# Bowlong_Machine.net
KiCad netlist of a schematic drawn in Altium Designer
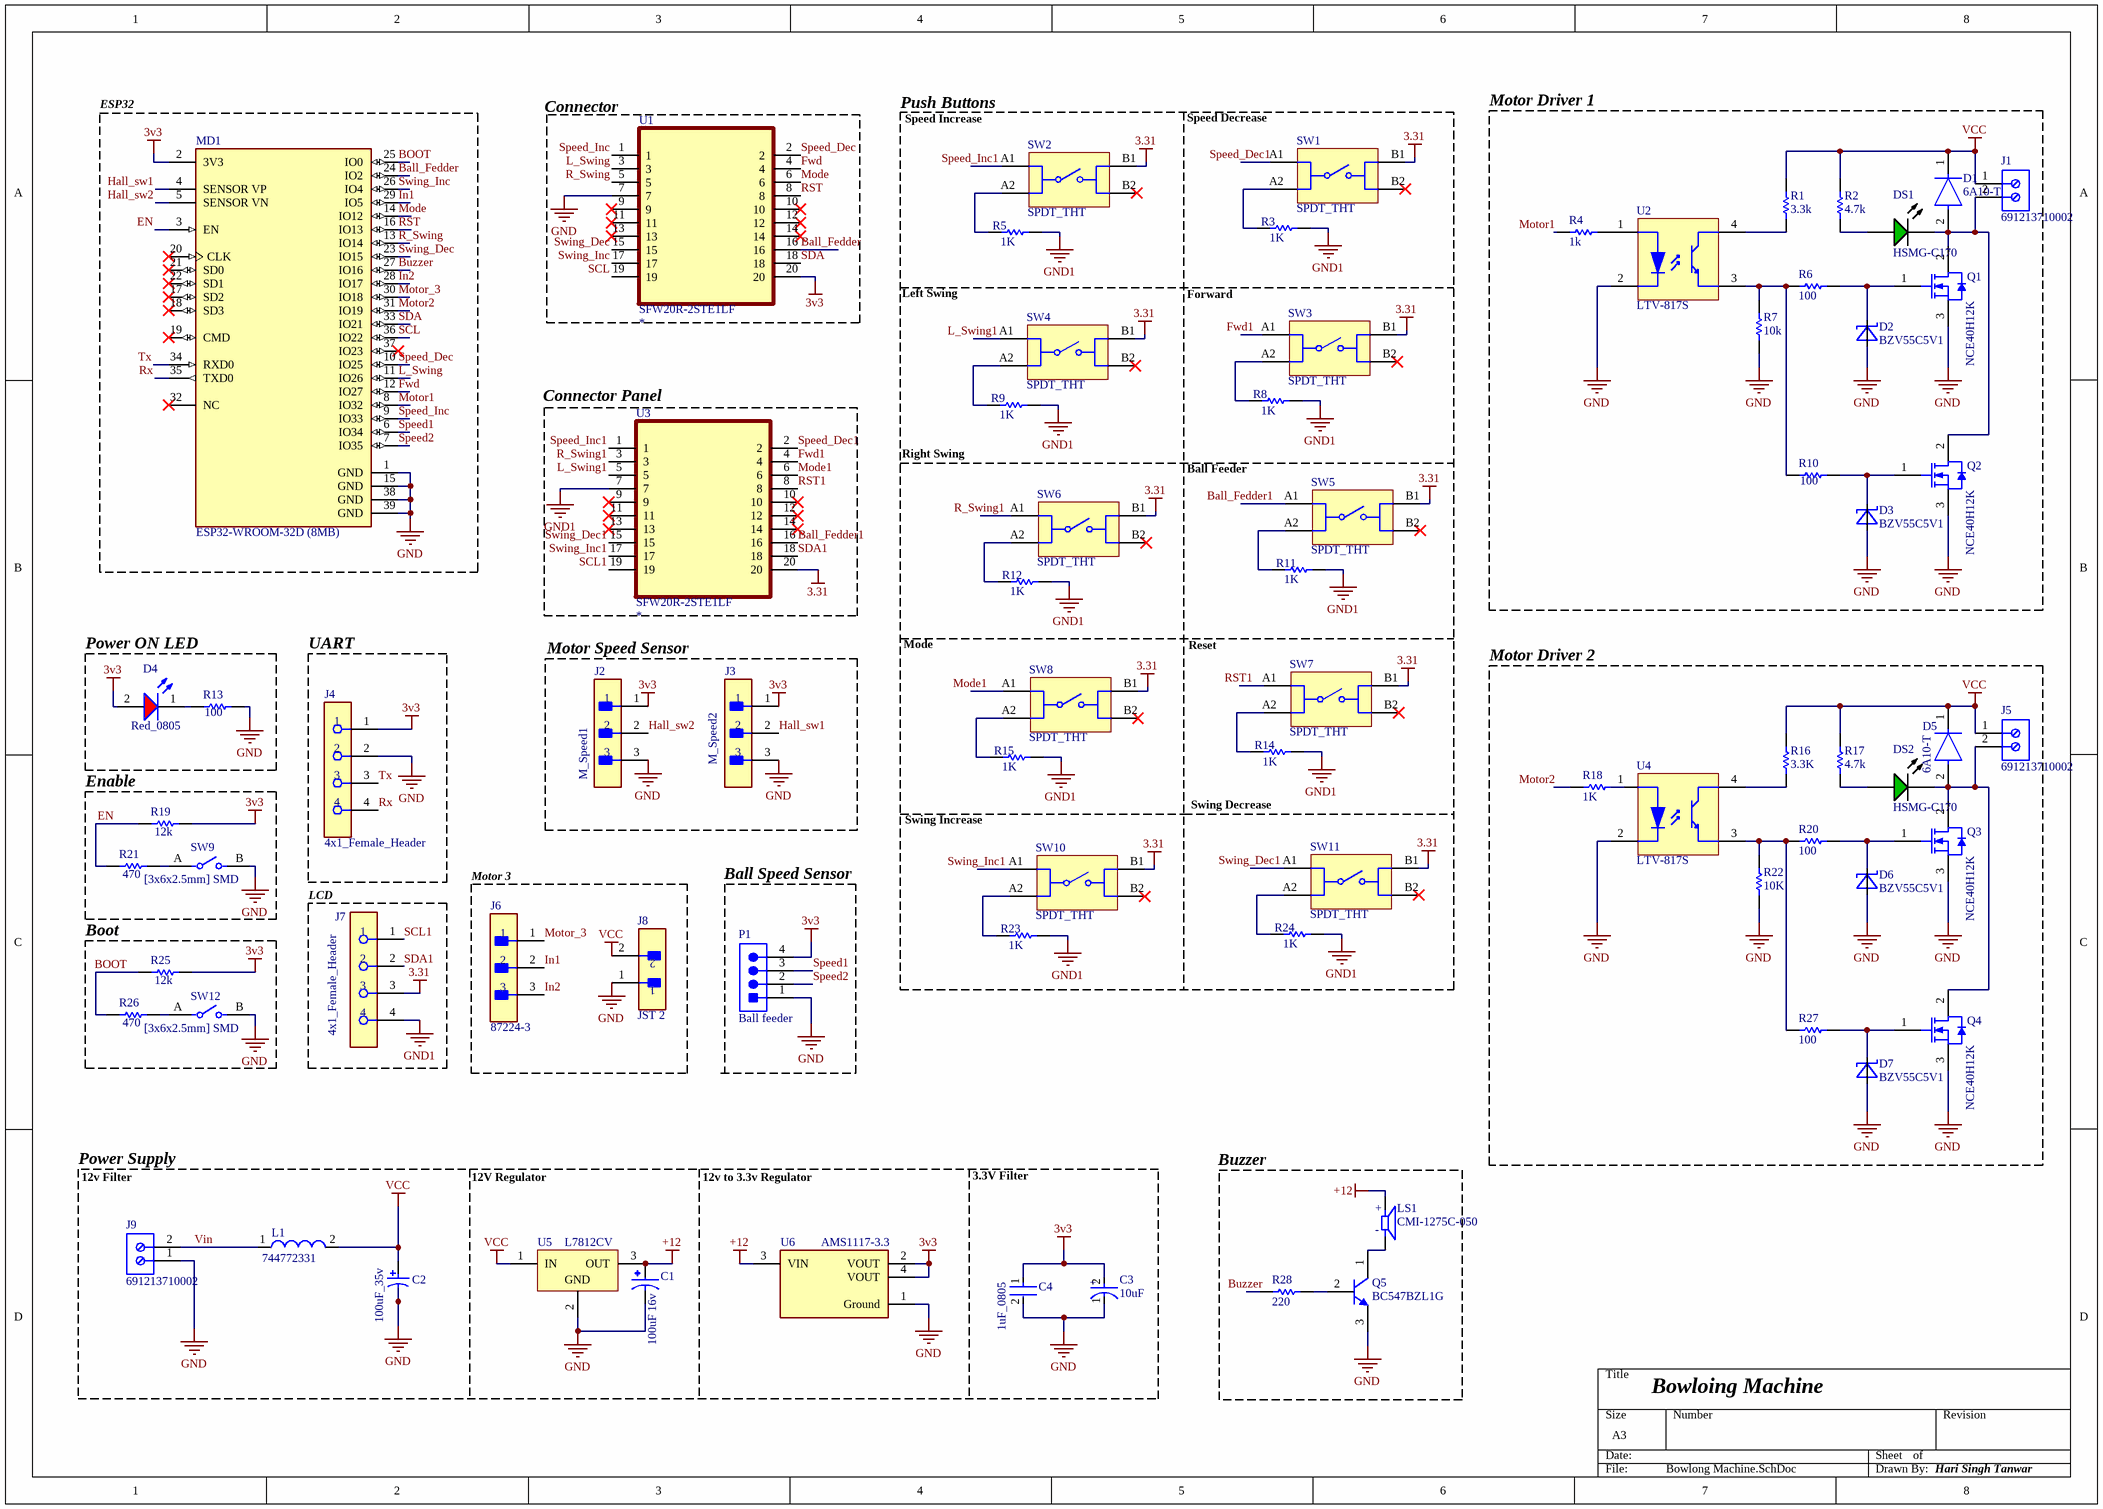
[diagram p0: Bowlong Machine.SchDoc]

(export (version "E")
  (design (tool "Eeschema 10.0.6"))
  (components
    (comp (ref "C1")
      (value "100uF 16v")
      (footprint "CAPPRD250W50D630H1120")
      (description "Cap Aluminum Lytic 100uF 16V 20% (6.3 X 11.2mm) Radial 2.5mm 290mA 1000h 105C Automotive Ammo")
      (fields (field (name "MF") "Panasonic") (field (name "MP") "EEU-FC1C101H"))
      (libsource (lib "100uF-16v-Capacitor") (part "EEUFC1C101H"))
    )
    (comp (ref "C2")
      (value "100uF_35v")
      (footprint "PNSC-EEU-EE2G100-2_V")
      (fields (field (name "PARTNUMBER") "EEU-EE2G100") (field (name "MANUFACTURER") "Panasonic"))
      (libsource (lib "Altium Content Vault") (part "PNSC-CAP-P-2"))
    )
    (comp (ref "C3")
      (value "10uF")
      (footprint "FP-SC-MFG")
      (description "CAP ALUM 10UF 20% 35V SMD")
      (fields (field (name "TOLERANCE") "20%") (field (name "VOLTAGE") "35V"))
      (libsource (lib "Altium Content Vault") (part "203bc49f2ac43e59fd269a8c329ed05"))
    )
    (comp (ref "C4")
      (value "1uF_0805")
      (footprint "FP-CC0805-0_85-MFG")
      (description "CAP CER 0.1UF 50V X7R 0805")
      (fields (field (name "TOLERANCE") "0.1") (field (name "MANUFACTURER PART NUMBER") "CC0805KRX7R9BB104"))
      (libsource (lib "Altium Content Vault") (part "11868f565c42a9108669ba33697ecf6"))
    )
    (comp (ref "D1")
      (value "6A10-T")
      (footprint "FP-R-6-MFG")
      (description "DIODE GEN PURP 1KV 6A R6")
      (fields
        (field (name "MANUFACTURER") "Diodes Inc.")
        (field (name "OCTOPART") "https://octopart.com/6a10-t-diodes+inc.-55426548")
      )
      (libsource (lib "Altium Content Vault") (part "d7152d700b627762746794eb795d46e"))
    )
    (comp (ref "D2")
      (value "BZV55C5V1")
      (footprint "MINIMELF-2")
      (description "Zener Diode 5.1 V 500 mW Â±5% Surface Mount LLDS; MiniMelf")
      (fields (field (name "MF") "Nexperia USA") (field (name "MP") "BZV55-C5V1"))
      (libsource (lib "BZV55C5V1") (part "BZV55C5V1"))
    )
    (comp (ref "D3")
      (value "BZV55C5V1")
      (footprint "MINIMELF-2")
      (description "Zener Diode 5.1 V 500 mW Â±5% Surface Mount LLDS; MiniMelf")
      (fields (field (name "MF") "Nexperia USA") (field (name "MP") "BZV55-C5V1"))
      (libsource (lib "BZV55C5V1") (part "BZV55C5V1"))
    )
    (comp (ref "D4")
      (value "Red_0805")
      (footprint "WL-SMCW_0805_150080xx75000")
      (libsource (lib "Altium Content Vault") (part "LED_Red_2A-1K"))
    )
    (comp (ref "D5")
      (value "6A10-T")
      (footprint "FP-R-6-MFG")
      (description "DIODE GEN PURP 1KV 6A R6")
      (fields
        (field (name "MANUFACTURER") "Diodes Inc.")
        (field (name "OCTOPART") "https://octopart.com/6a10-t-diodes+inc.-55426548")
      )
      (libsource (lib "Altium Content Vault") (part "d7152d700b627762746794eb795d46e"))
    )
    (comp (ref "D6")
      (value "BZV55C5V1")
      (footprint "MINIMELF-2")
      (description "Zener Diode 5.1 V 500 mW Â±5% Surface Mount LLDS; MiniMelf")
      (fields (field (name "MF") "Nexperia USA") (field (name "MP") "BZV55-C5V1"))
      (libsource (lib "BZV55C5V1") (part "BZV55C5V1"))
    )
    (comp (ref "D7")
      (value "BZV55C5V1")
      (footprint "MINIMELF-2")
      (description "Zener Diode 5.1 V 500 mW Â±5% Surface Mount LLDS; MiniMelf")
      (fields (field (name "MF") "Nexperia USA") (field (name "MP") "BZV55-C5V1"))
      (libsource (lib "BZV55C5V1") (part "BZV55C5V1"))
    )
    (comp (ref "DS1")
      (value "HSMG-C170")
      (footprint "AVAG-HSMX-C170_V")
      (description "Chip LED, Green, 2.2 V, -40 to 85 degC, 2-Pin SMD, Pb-Free, Tape and Reel")
      (fields (field (name "MANUFACTURER") "Avago"))
      (libsource (lib "Altium Content Vault") (part "LED_GREEN_A1K2-2"))
    )
    (comp (ref "DS2")
      (value "HSMG-C170")
      (footprint "AVAG-HSMX-C170_V")
      (description "Chip LED, Green, 2.2 V, -40 to 85 degC, 2-Pin SMD, Pb-Free, Tape and Reel")
      (fields (field (name "MANUFACTURER") "Avago"))
      (libsource (lib "Altium Content Vault") (part "LED_GREEN_A1K2-2"))
    )
    (comp (ref "J1")
      (value "691213710002")
      (footprint "691213710002")
      (fields (field (name "VOLTAGE") "300V"))
      (libsource (lib "Altium Content Vault") (part "TBL - 1R - 02P - Screw"))
    )
    (comp (ref "J2")
      (value "M_Speed1")
      (footprint "FP-B3B-XH-A_LF_SN-MFG")
      (description "CONN HEADER VERT 3POS 2.5MM")
      (libsource (lib "Altium Content Vault") (part "0d3f023dd272f625e17a2be33dea85f"))
    )
    (comp (ref "J3")
      (value "M_Speed2")
      (footprint "FP-B3B-XH-A_LF_SN-MFG")
      (description "CONN HEADER VERT 3POS 2.5MM")
      (libsource (lib "Altium Content Vault") (part "0d3f023dd272f625e17a2be33dea85f"))
    )
    (comp (ref "J4")
      (value "4x1_Female_Header")
      (footprint "FP-2212S-04SG-85-MFG")
      (description "Header, Rectangular, 4 Positions, 2.54mm Pitch, Receptacle, Vertical, Through-Hole")
      (libsource (lib "Altium Content Vault") (part "56792406a6bd5c25e158f553ecd1aa7"))
    )
    (comp (ref "J5")
      (value "691213710002")
      (footprint "691213710002")
      (fields (field (name "VOLTAGE") "300V"))
      (libsource (lib "Altium Content Vault") (part "TBL - 1R - 02P - Screw"))
    )
    (comp (ref "J6")
      (value "87224-3")
      (footprint "FP-87224-3-MFG")
      (description "CONN HEADER VERT 3POS 2.54MM")
      (libsource (lib "Altium Content Vault") (part "0d3f023dd272f625e17a2be33dea85f"))
    )
    (comp (ref "J7")
      (value "4x1_Female_Header")
      (footprint "FP-2212S-04SG-85-MFG")
      (description "Header, Rectangular, 4 Positions, 2.54mm Pitch, Receptacle, Vertical, Through-Hole")
      (libsource (lib "Altium Content Vault") (part "56792406a6bd5c25e158f553ecd1aa7"))
    )
    (comp (ref "J8")
      (value "JST 2")
      (footprint "FP-B2B-XH-A_LF_SN-MFG")
      (description "CONN HEADER VERT 2POS 2.5MM")
      (libsource (lib "Altium Content Vault") (part "3bc925449376181038e59eaffc5286c"))
    )
    (comp (ref "J9")
      (value "691213710002")
      (footprint "691213710002")
      (fields (field (name "VOLTAGE") "300V"))
      (libsource (lib "Altium Content Vault") (part "TBL - 1R - 02P - Screw"))
    )
    (comp (ref "L1")
      (value "744772331")
      (footprint "WE-TI-L")
      (description "Radial Leaded Wire Wound Inductor WE-TI, L=330 µH")
      (fields (field (name "MANUFACTURER") "Wuerth Elektronik"))
      (libsource (lib "Altium Content Vault") (part "PAS-IND-INDUCTOR-2"))
    )
    (comp (ref "LS1")
      (value "CMI-1275C-050")
      (footprint "CUI_CMI-1275C-050")
      (description "12 mm, 5 Vdc, 90 dB, 3.1 kHz, Through Hole, Magnetic Audio Indicator Buzzer")
      (fields (field (name "MF") "CUI Devices"))
      (libsource (lib "BUZZER-1275C-050") (part "CMI-1275C-050"))
    )
    (comp (ref "MD1")
      (value "ESP32-WROOM-32D (8MB)")
      (footprint "FP-ESP32-WROOM-32D_8MB-MFG")
      (description "RX TXRX MOD WIFI TRACE ANT SMD")
      (libsource (lib "Altium Content Vault") (part "f49400bffd2bcd917121b26d8c3f628"))
    )
    (comp (ref "P1")
      (value "Ball feeder")
      (footprint "JST-B4B-EH-A_V")
      (fields (field (name "MANUFACTURER") "JST"))
      (libsource (lib "Altium Content Vault") (part "CN-1P-M-R4"))
    )
    (comp (ref "Q1")
      (value "NCE40H12K")
      (footprint "INF-PG-TO252-3-313_N")
      (fields (field (name "MANUFACTURER") "Infineon") (field (name "PARTNUMBER") "IPD60R520C6"))
      (libsource (lib "Altium Content Vault") (part "INF-NEMOS-GDS-3"))
    )
    (comp (ref "Q2")
      (value "NCE40H12K")
      (footprint "INF-PG-TO252-3-313_N")
      (fields (field (name "MANUFACTURER") "Infineon") (field (name "PARTNUMBER") "IPD60R520C6"))
      (libsource (lib "Altium Content Vault") (part "INF-NEMOS-GDS-3"))
    )
    (comp (ref "Q3")
      (value "NCE40H12K")
      (footprint "INF-PG-TO252-3-313_N")
      (fields (field (name "MANUFACTURER") "Infineon") (field (name "PARTNUMBER") "IPD60R520C6"))
      (libsource (lib "Altium Content Vault") (part "INF-NEMOS-GDS-3"))
    )
    (comp (ref "Q4")
      (value "NCE40H12K")
      (footprint "INF-PG-TO252-3-313_N")
      (fields (field (name "MANUFACTURER") "Infineon") (field (name "PARTNUMBER") "IPD60R520C6"))
      (libsource (lib "Altium Content Vault") (part "INF-NEMOS-GDS-3"))
    )
    (comp (ref "Q5")
      (value "BC547BZL1G")
      (footprint "ONSC-TO-92-3-29-11_AM_BL")
      (description "Amplifier Transistor, NPN Silicon, 3-Pin TO-92, Pb-Free, Ammo Box")
      (fields (field (name "MANUFACTURER") "On Semiconductor"))
      (libsource (lib "Altium Content Vault") (part "ONSC-NPN-C1B2E3-3"))
    )
    (comp (ref "R1")
      (value "3.3k")
      (footprint "RESC2013X50X30LL20T20")
      (fields (field (name "MANUFACTURER") "Vishay Dale") (field (name "PART NUMBER") "CRCW08050000Z0EA"))
      (libsource (lib "Altium Content Vault") (part "RES"))
    )
    (comp (ref "R2")
      (value "4.7k")
      (footprint "RESC2013X50X30LL20T20")
      (fields (field (name "MANUFACTURER") "Vishay Dale") (field (name "PART NUMBER") "CRCW08050000Z0EA"))
      (libsource (lib "Altium Content Vault") (part "RES"))
    )
    (comp (ref "R3")
      (value "1K")
      (footprint "RESC2013X50X30LL20T20")
      (fields (field (name "MANUFACTURER") "Vishay Dale") (field (name "PART NUMBER") "CRCW08050000Z0EA"))
      (libsource (lib "Altium Content Vault") (part "RES"))
    )
    (comp (ref "R4")
      (value "1k")
      (footprint "RESC2013X50X30LL20T20")
      (fields (field (name "MANUFACTURER") "Vishay Dale") (field (name "PART NUMBER") "CRCW08050000Z0EA"))
      (libsource (lib "Altium Content Vault") (part "RES"))
    )
    (comp (ref "R5")
      (value "1K")
      (footprint "RESC2013X50X30LL20T20")
      (fields (field (name "MANUFACTURER") "Vishay Dale") (field (name "PART NUMBER") "CRCW08050000Z0EA"))
      (libsource (lib "Altium Content Vault") (part "RES"))
    )
    (comp (ref "R6")
      (value "100")
      (footprint "RESC2013X50X30LL20T20")
      (fields (field (name "MANUFACTURER") "Vishay Dale") (field (name "PART NUMBER") "CRCW08050000Z0EA"))
      (libsource (lib "Altium Content Vault") (part "RES"))
    )
    (comp (ref "R7")
      (value "10k")
      (footprint "RESC2013X50X30LL20T20")
      (fields (field (name "MANUFACTURER") "Vishay Dale") (field (name "PART NUMBER") "CRCW08050000Z0EA"))
      (libsource (lib "Altium Content Vault") (part "RES"))
    )
    (comp (ref "R8")
      (value "1K")
      (footprint "RESC2013X50X30LL20T20")
      (fields (field (name "MANUFACTURER") "Vishay Dale") (field (name "PART NUMBER") "CRCW08050000Z0EA"))
      (libsource (lib "Altium Content Vault") (part "RES"))
    )
    (comp (ref "R9")
      (value "1K")
      (footprint "RESC2013X50X30LL20T20")
      (fields (field (name "MANUFACTURER") "Vishay Dale") (field (name "PART NUMBER") "CRCW08050000Z0EA"))
      (libsource (lib "Altium Content Vault") (part "RES"))
    )
    (comp (ref "R10")
      (value "100")
      (footprint "RESC2013X50X30LL20T20")
      (fields (field (name "MANUFACTURER") "Vishay Dale") (field (name "PART NUMBER") "CRCW08050000Z0EA"))
      (libsource (lib "Altium Content Vault") (part "RES"))
    )
    (comp (ref "R11")
      (value "1K")
      (footprint "RESC2013X50X30LL20T20")
      (fields (field (name "MANUFACTURER") "Vishay Dale") (field (name "PART NUMBER") "CRCW08050000Z0EA"))
      (libsource (lib "Altium Content Vault") (part "RES"))
    )
    (comp (ref "R12")
      (value "1K")
      (footprint "RESC2013X50X30LL20T20")
      (fields (field (name "MANUFACTURER") "Vishay Dale") (field (name "PART NUMBER") "CRCW08050000Z0EA"))
      (libsource (lib "Altium Content Vault") (part "RES"))
    )
    (comp (ref "R13")
      (value "100")
      (footprint "RESC2013X50X30LL20T20")
      (fields (field (name "MANUFACTURER") "Vishay Dale") (field (name "PART NUMBER") "CRCW08050000Z0EA"))
      (libsource (lib "Altium Content Vault") (part "RES"))
    )
    (comp (ref "R14")
      (value "1K")
      (footprint "RESC2013X50X30LL20T20")
      (fields (field (name "MANUFACTURER") "Vishay Dale") (field (name "PART NUMBER") "CRCW08050000Z0EA"))
      (libsource (lib "Altium Content Vault") (part "RES"))
    )
    (comp (ref "R15")
      (value "1K")
      (footprint "RESC2013X50X30LL20T20")
      (fields (field (name "MANUFACTURER") "Vishay Dale") (field (name "PART NUMBER") "CRCW08050000Z0EA"))
      (libsource (lib "Altium Content Vault") (part "RES"))
    )
    (comp (ref "R16")
      (value "3.3K")
      (footprint "RESC2013X50X30LL20T20")
      (fields (field (name "MANUFACTURER") "Vishay Dale") (field (name "PART NUMBER") "CRCW08050000Z0EA"))
      (libsource (lib "Altium Content Vault") (part "RES"))
    )
    (comp (ref "R17")
      (value "4.7k")
      (footprint "RESC2013X50X30LL20T20")
      (fields (field (name "MANUFACTURER") "Vishay Dale") (field (name "PART NUMBER") "CRCW08050000Z0EA"))
      (libsource (lib "Altium Content Vault") (part "RES"))
    )
    (comp (ref "R18")
      (value "1K")
      (footprint "RESC2013X50X30LL20T20")
      (fields (field (name "MANUFACTURER") "Vishay Dale") (field (name "PART NUMBER") "CRCW08050000Z0EA"))
      (libsource (lib "Altium Content Vault") (part "RES"))
    )
    (comp (ref "R19")
      (value "12k")
      (footprint "RESC2013X50X30LL20T20")
      (fields (field (name "MANUFACTURER") "Vishay Dale") (field (name "PART NUMBER") "CRCW08050000Z0EA"))
      (libsource (lib "Altium Content Vault") (part "RES"))
    )
    (comp (ref "R20")
      (value "100")
      (footprint "RESC2013X50X30LL20T20")
      (fields (field (name "MANUFACTURER") "Vishay Dale") (field (name "PART NUMBER") "CRCW08050000Z0EA"))
      (libsource (lib "Altium Content Vault") (part "RES"))
    )
    (comp (ref "R21")
      (value "470")
      (footprint "RESC2013X50X30LL20T20")
      (fields (field (name "MANUFACTURER") "Vishay Dale") (field (name "PART NUMBER") "CRCW08050000Z0EA"))
      (libsource (lib "Altium Content Vault") (part "RES"))
    )
    (comp (ref "R22")
      (value "10K")
      (footprint "RESC2013X50X30LL20T20")
      (fields (field (name "MANUFACTURER") "Vishay Dale") (field (name "PART NUMBER") "CRCW08050000Z0EA"))
      (libsource (lib "Altium Content Vault") (part "RES"))
    )
    (comp (ref "R23")
      (value "1K")
      (footprint "RESC2013X50X30LL20T20")
      (fields (field (name "MANUFACTURER") "Vishay Dale") (field (name "PART NUMBER") "CRCW08050000Z0EA"))
      (libsource (lib "Altium Content Vault") (part "RES"))
    )
    (comp (ref "R24")
      (value "1K")
      (footprint "RESC2013X50X30LL20T20")
      (fields (field (name "MANUFACTURER") "Vishay Dale") (field (name "PART NUMBER") "CRCW08050000Z0EA"))
      (libsource (lib "Altium Content Vault") (part "RES"))
    )
    (comp (ref "R25")
      (value "12k")
      (footprint "RESC2013X50X30LL20T20")
      (fields (field (name "MANUFACTURER") "Vishay Dale") (field (name "PART NUMBER") "CRCW08050000Z0EA"))
      (libsource (lib "Altium Content Vault") (part "RES"))
    )
    (comp (ref "R26")
      (value "470")
      (footprint "RESC2013X50X30LL20T20")
      (fields (field (name "MANUFACTURER") "Vishay Dale") (field (name "PART NUMBER") "CRCW08050000Z0EA"))
      (libsource (lib "Altium Content Vault") (part "RES"))
    )
    (comp (ref "R27")
      (value "100")
      (footprint "RESC2013X50X30LL20T20")
      (fields (field (name "MANUFACTURER") "Vishay Dale") (field (name "PART NUMBER") "CRCW08050000Z0EA"))
      (libsource (lib "Altium Content Vault") (part "RES"))
    )
    (comp (ref "R28")
      (value "220")
      (footprint "RESC2013X50X30LL20T20")
      (fields (field (name "MANUFACTURER") "Vishay Dale") (field (name "PART NUMBER") "CRCW08050000Z0EA"))
      (libsource (lib "Altium Content Vault") (part "RES"))
    )
    (comp (ref "SW1")
      (value "SPDT_THT")
      (footprint "4301x60707x6")
      (libsource (lib "Altium Content Vault") (part "SPST-NO_4P"))
    )
    (comp (ref "SW2")
      (value "SPDT_THT")
      (footprint "4301x60707x6")
      (libsource (lib "Altium Content Vault") (part "SPST-NO_4P"))
    )
    (comp (ref "SW3")
      (value "SPDT_THT")
      (footprint "4301x60707x6")
      (libsource (lib "Altium Content Vault") (part "SPST-NO_4P"))
    )
    (comp (ref "SW4")
      (value "SPDT_THT")
      (footprint "4301x60707x6")
      (libsource (lib "Altium Content Vault") (part "SPST-NO_4P"))
    )
    (comp (ref "SW5")
      (value "SPDT_THT")
      (footprint "4301x60707x6")
      (libsource (lib "Altium Content Vault") (part "SPST-NO_4P"))
    )
    (comp (ref "SW6")
      (value "SPDT_THT")
      (footprint "4301x60707x6")
      (libsource (lib "Altium Content Vault") (part "SPST-NO_4P"))
    )
    (comp (ref "SW7")
      (value "SPDT_THT")
      (footprint "4301x60707x6")
      (libsource (lib "Altium Content Vault") (part "SPST-NO_4P"))
    )
    (comp (ref "SW8")
      (value "SPDT_THT")
      (footprint "4301x60707x6")
      (libsource (lib "Altium Content Vault") (part "SPST-NO_4P"))
    )
    (comp (ref "SW9")
      (value "[3x6x2.5mm] SMD")
      (footprint "FP-EVQ-PE105K-MFG")
      (description "EVQ-PE105K Switch Tactile N.O. SPST Rectangular Button J-Bend 0.05A 12VDC 1N SMD Embossed Tape")
      (libsource (lib "Altium Content Vault") (part "2b0b2b19372efd94fa7681498149756"))
    )
    (comp (ref "SW10")
      (value "SPDT_THT")
      (footprint "4301x60707x6")
      (libsource (lib "Altium Content Vault") (part "SPST-NO_4P"))
    )
    (comp (ref "SW11")
      (value "SPDT_THT")
      (footprint "4301x60707x6")
      (libsource (lib "Altium Content Vault") (part "SPST-NO_4P"))
    )
    (comp (ref "SW12")
      (value "[3x6x2.5mm] SMD")
      (footprint "FP-EVQ-PE105K-MFG")
      (description "EVQ-PE105K Switch Tactile N.O. SPST Rectangular Button J-Bend 0.05A 12VDC 1N SMD Embossed Tape")
      (libsource (lib "Altium Content Vault") (part "2b0b2b19372efd94fa7681498149756"))
    )
    (comp (ref "U1")
      (value "SFW20R-2STE1LF")
      (footprint "FCI_SFW20R-2STE1LF")
      (description "FFC/FPC CONNECTOR, RECEPTACLE 20POS 1ROW")
      (fields (field (name "ALTIUM_VALUE") "*"))
      (libsource (lib "Government Engineering College Bikaner") (part "SFW20R-2STE1LF"))
    )
    (comp (ref "U2")
      (value "LTV-817S")
      (footprint "LTST-LTV-817S-4_V")
      (description "Photocoupler - Phototransistor Output, 35 V VCEO, -50 to 110 degC, 4-Pin SMD, RoHS, Tape and Reel")
      (fields (field (name "MANUFACTURER") "Lite-On"))
      (libsource (lib "Altium Content Vault") (part "LTST-LTV-817-4"))
    )
    (comp (ref "U3")
      (value "SFW20R-2STE1LF")
      (footprint "FCI_SFW20R-2STE1LF")
      (description "FFC/FPC CONNECTOR, RECEPTACLE 20POS 1ROW")
      (fields (field (name "ALTIUM_VALUE") "*"))
      (libsource (lib "Government Engineering College Bikaner") (part "SFW20R-2STE1LF"))
    )
    (comp (ref "U4")
      (value "LTV-817S")
      (footprint "LTST-LTV-817S-4_V")
      (description "Photocoupler - Phototransistor Output, 35 V VCEO, -50 to 110 degC, 4-Pin SMD, RoHS, Tape and Reel")
      (fields (field (name "MANUFACTURER") "Lite-On"))
      (libsource (lib "Altium Content Vault") (part "LTST-LTV-817-4"))
    )
    (comp (ref "U5")
      (value "L7812CV")
      (footprint "TO220")
      (description "Positive Voltage Regulator, 12V, 3-Pin TO-220")
      (libsource (lib "Altium Content Vault") (part "PM-REG-L4940-SIL3"))
    )
    (comp (ref "U6")
      (value "AMS1117-3.3")
      (footprint "FP-AMS1117-IPC_C")
      (description "LDO Voltage Regulators 1A, 3.3V")
      (fields
        (field (name "OCTOPART") "https://octopart.com/ams1117-3.3-advanced+monolithic+systems-25899300")
        (field (name "MANUFACTURER") "Advanced Monolithic Systems")
      )
      (libsource (lib "Altium Content Vault") (part "8bdbb5f8e77002000e30dd2845d0354"))
    )
  )
  (nets
    (net (code "1") (name "+12") (class "Default")
      (node (ref "C1") (pin "P") (pinfunction "P_P") (pintype "passive"))
      (node (ref "LS1") (pin "P") (pinfunction "P_P") (pintype "passive"))
      (node (ref "U5") (pin "3") (pinfunction "OUT_3") (pintype "power_in"))
      (node (ref "U6") (pin "3") (pinfunction "VIN_3") (pintype "power_in"))
    )
    (net (code "2") (name "/BOOT") (class "Default")
      (node (ref "MD1") (pin "25") (pinfunction "IO0_25") (pintype "bidirectional"))
      (node (ref "R25") (pin "2") (pinfunction "2_2") (pintype "passive"))
      (node (ref "R26") (pin "2") (pinfunction "2_2") (pintype "passive"))
    )
    (net (code "3") (name "/Ball_Fedder") (class "Default")
      (node (ref "MD1") (pin "24") (pinfunction "IO2_24") (pintype "bidirectional"))
      (node (ref "U1") (pin "16") (pinfunction "16_16") (pintype "passive"))
    )
    (net (code "4") (name "/Ball_Fedder1") (class "Default")
      (node (ref "SW5") (pin "A1") (pinfunction "A1_A1") (pintype "passive"))
      (node (ref "U3") (pin "16") (pinfunction "16_16") (pintype "passive"))
    )
    (net (code "5") (name "/Buzzer") (class "Default")
      (node (ref "MD1") (pin "27") (pinfunction "IO16_27") (pintype "bidirectional"))
      (node (ref "R28") (pin "1") (pinfunction "1_1") (pintype "passive"))
    )
    (net (code "6") (name "/EN") (class "Default")
      (node (ref "MD1") (pin "3") (pinfunction "EN_3") (pintype "input"))
      (node (ref "R19") (pin "2") (pinfunction "2_2") (pintype "passive"))
      (node (ref "R21") (pin "2") (pinfunction "2_2") (pintype "passive"))
    )
    (net (code "7") (name "/Fwd") (class "Default")
      (node (ref "MD1") (pin "12") (pinfunction "IO27_12") (pintype "bidirectional"))
      (node (ref "U1") (pin "4") (pinfunction "4_4") (pintype "passive"))
    )
    (net (code "8") (name "/Fwd1") (class "Default")
      (node (ref "SW3") (pin "A1") (pinfunction "A1_A1") (pintype "passive"))
      (node (ref "U3") (pin "4") (pinfunction "4_4") (pintype "passive"))
    )
    (net (code "9") (name "/Hall_sw1") (class "Default")
      (node (ref "J3") (pin "2") (pinfunction "2_2") (pintype "passive"))
      (node (ref "MD1") (pin "4") (pinfunction "SENSOR_VP_4") (pintype "passive"))
    )
    (net (code "10") (name "/Hall_sw2") (class "Default")
      (node (ref "J2") (pin "2") (pinfunction "2_2") (pintype "passive"))
      (node (ref "MD1") (pin "5") (pinfunction "SENSOR_VN_5") (pintype "passive"))
    )
    (net (code "11") (name "/In1") (class "Default")
      (node (ref "J6") (pin "2") (pinfunction "2_2") (pintype "passive"))
      (node (ref "MD1") (pin "29") (pinfunction "IO5_29") (pintype "bidirectional"))
    )
    (net (code "12") (name "/In2") (class "Default")
      (node (ref "J6") (pin "3") (pinfunction "3_3") (pintype "passive"))
      (node (ref "MD1") (pin "28") (pinfunction "IO17_28") (pintype "bidirectional"))
    )
    (net (code "13") (name "/L_Swing") (class "Default")
      (node (ref "MD1") (pin "11") (pinfunction "IO26_11") (pintype "bidirectional"))
      (node (ref "U1") (pin "3") (pinfunction "3_3") (pintype "passive"))
    )
    (net (code "14") (name "/L_Swing1") (class "Default")
      (node (ref "SW4") (pin "A1") (pinfunction "A1_A1") (pintype "passive"))
      (node (ref "U3") (pin "5") (pinfunction "5_5") (pintype "passive"))
    )
    (net (code "15") (name "/Mode") (class "Default")
      (node (ref "MD1") (pin "14") (pinfunction "IO12_14") (pintype "bidirectional"))
      (node (ref "U1") (pin "6") (pinfunction "6_6") (pintype "passive"))
    )
    (net (code "16") (name "/Mode1") (class "Default")
      (node (ref "SW8") (pin "A1") (pinfunction "A1_A1") (pintype "passive"))
      (node (ref "U3") (pin "6") (pinfunction "6_6") (pintype "passive"))
    )
    (net (code "17") (name "/Motor1") (class "Default")
      (node (ref "MD1") (pin "8") (pinfunction "IO32_8") (pintype "bidirectional"))
      (node (ref "R4") (pin "1") (pinfunction "1_1") (pintype "passive"))
    )
    (net (code "18") (name "/Motor2") (class "Default")
      (node (ref "MD1") (pin "31") (pinfunction "IO19_31") (pintype "bidirectional"))
      (node (ref "R18") (pin "1") (pinfunction "1_1") (pintype "passive"))
    )
    (net (code "19") (name "/Motor_3") (class "Default")
      (node (ref "J6") (pin "1") (pinfunction "1_1") (pintype "passive"))
      (node (ref "MD1") (pin "30") (pinfunction "IO18_30") (pintype "bidirectional"))
    )
    (net (code "20") (name "/RST") (class "Default")
      (node (ref "MD1") (pin "16") (pinfunction "IO13_16") (pintype "bidirectional"))
      (node (ref "U1") (pin "8") (pinfunction "8_8") (pintype "passive"))
    )
    (net (code "21") (name "/RST1") (class "Default")
      (node (ref "SW7") (pin "A1") (pinfunction "A1_A1") (pintype "passive"))
      (node (ref "U3") (pin "8") (pinfunction "8_8") (pintype "passive"))
    )
    (net (code "22") (name "/R_Swing") (class "Default")
      (node (ref "MD1") (pin "13") (pinfunction "IO14_13") (pintype "bidirectional"))
      (node (ref "U1") (pin "5") (pinfunction "5_5") (pintype "passive"))
    )
    (net (code "23") (name "/R_Swing1") (class "Default")
      (node (ref "SW6") (pin "A1") (pinfunction "A1_A1") (pintype "passive"))
      (node (ref "U3") (pin "3") (pinfunction "3_3") (pintype "passive"))
    )
    (net (code "24") (name "/Rx") (class "Default")
      (node (ref "J4") (pin "4") (pinfunction "4_4") (pintype "passive"))
      (node (ref "MD1") (pin "35") (pinfunction "TXD0_35") (pintype "output"))
    )
    (net (code "25") (name "/SCL") (class "Default")
      (node (ref "MD1") (pin "36") (pinfunction "IO22_36") (pintype "bidirectional"))
      (node (ref "U1") (pin "19") (pinfunction "19_19") (pintype "passive"))
    )
    (net (code "26") (name "/SCL1") (class "Default")
      (node (ref "J7") (pin "1") (pinfunction "1_1") (pintype "passive"))
      (node (ref "U3") (pin "19") (pinfunction "19_19") (pintype "passive"))
    )
    (net (code "27") (name "/SDA") (class "Default")
      (node (ref "MD1") (pin "33") (pinfunction "IO21_33") (pintype "bidirectional"))
      (node (ref "U1") (pin "18") (pinfunction "18_18") (pintype "passive"))
    )
    (net (code "28") (name "/SDA1") (class "Default")
      (node (ref "J7") (pin "2") (pinfunction "2_2") (pintype "passive"))
      (node (ref "U3") (pin "18") (pinfunction "18_18") (pintype "passive"))
    )
    (net (code "29") (name "/Speed1") (class "Default")
      (node (ref "MD1") (pin "6") (pinfunction "IO34_6") (pintype "bidirectional"))
      (node (ref "P1") (pin "3") (pinfunction "3_3") (pintype "passive"))
    )
    (net (code "30") (name "/Speed2") (class "Default")
      (node (ref "MD1") (pin "7") (pinfunction "IO35_7") (pintype "bidirectional"))
      (node (ref "P1") (pin "2") (pinfunction "2_2") (pintype "passive"))
    )
    (net (code "31") (name "/Speed_Dec") (class "Default")
      (node (ref "MD1") (pin "10") (pinfunction "IO25_10") (pintype "bidirectional"))
      (node (ref "U1") (pin "2") (pinfunction "2_2") (pintype "passive"))
    )
    (net (code "32") (name "/Speed_Dec1") (class "Default")
      (node (ref "SW1") (pin "A1") (pinfunction "A1_A1") (pintype "passive"))
      (node (ref "U3") (pin "2") (pinfunction "2_2") (pintype "passive"))
    )
    (net (code "33") (name "/Speed_Inc") (class "Default")
      (node (ref "MD1") (pin "9") (pinfunction "IO33_9") (pintype "bidirectional"))
      (node (ref "U1") (pin "1") (pinfunction "1_1") (pintype "passive"))
    )
    (net (code "34") (name "/Speed_Inc1") (class "Default")
      (node (ref "SW2") (pin "A1") (pinfunction "A1_A1") (pintype "passive"))
      (node (ref "U3") (pin "1") (pinfunction "1_1") (pintype "passive"))
    )
    (net (code "35") (name "/Swing_Dec") (class "Default")
      (node (ref "MD1") (pin "23") (pinfunction "IO15_23") (pintype "bidirectional"))
      (node (ref "U1") (pin "15") (pinfunction "15_15") (pintype "passive"))
    )
    (net (code "36") (name "/Swing_Dec1") (class "Default")
      (node (ref "SW11") (pin "A1") (pinfunction "A1_A1") (pintype "passive"))
      (node (ref "U3") (pin "15") (pinfunction "15_15") (pintype "passive"))
    )
    (net (code "37") (name "/Swing_Inc") (class "Default")
      (node (ref "MD1") (pin "26") (pinfunction "IO4_26") (pintype "bidirectional"))
      (node (ref "U1") (pin "17") (pinfunction "17_17") (pintype "passive"))
    )
    (net (code "38") (name "/Swing_Inc1") (class "Default")
      (node (ref "SW10") (pin "A1") (pinfunction "A1_A1") (pintype "passive"))
      (node (ref "U3") (pin "17") (pinfunction "17_17") (pintype "passive"))
    )
    (net (code "39") (name "/Tx") (class "Default")
      (node (ref "J4") (pin "3") (pinfunction "3_3") (pintype "passive"))
      (node (ref "MD1") (pin "34") (pinfunction "RXD0_34") (pintype "input"))
    )
    (net (code "40") (name "/Vin") (class "Default")
      (node (ref "J9") (pin "2") (pinfunction "2_2") (pintype "passive"))
      (node (ref "L1") (pin "1") (pinfunction "1_1") (pintype "passive"))
    )
    (net (code "41") (name "3.31") (class "Default")
      (node (ref "J7") (pin "3") (pinfunction "3_3") (pintype "passive"))
      (node (ref "SW1") (pin "B1") (pinfunction "B1_B1") (pintype "passive"))
      (node (ref "SW10") (pin "B1") (pinfunction "B1_B1") (pintype "passive"))
      (node (ref "SW11") (pin "B1") (pinfunction "B1_B1") (pintype "passive"))
      (node (ref "SW2") (pin "B1") (pinfunction "B1_B1") (pintype "passive"))
      (node (ref "SW3") (pin "B1") (pinfunction "B1_B1") (pintype "passive"))
      (node (ref "SW4") (pin "B1") (pinfunction "B1_B1") (pintype "passive"))
      (node (ref "SW5") (pin "B1") (pinfunction "B1_B1") (pintype "passive"))
      (node (ref "SW6") (pin "B1") (pinfunction "B1_B1") (pintype "passive"))
      (node (ref "SW7") (pin "B1") (pinfunction "B1_B1") (pintype "passive"))
      (node (ref "SW8") (pin "B1") (pinfunction "B1_B1") (pintype "passive"))
      (node (ref "U3") (pin "20") (pinfunction "20_20") (pintype "passive"))
    )
    (net (code "42") (name "3v3") (class "Default")
      (node (ref "C3") (pin "2") (pinfunction "A_2") (pintype "passive"))
      (node (ref "C4") (pin "1") (pinfunction "1_1") (pintype "passive"))
      (node (ref "D4") (pin "2") (pinfunction "A_2") (pintype "passive"))
      (node (ref "J2") (pin "1") (pinfunction "1_1") (pintype "passive"))
      (node (ref "J3") (pin "1") (pinfunction "1_1") (pintype "passive"))
      (node (ref "J4") (pin "1") (pinfunction "1_1") (pintype "passive"))
      (node (ref "MD1") (pin "2") (pinfunction "3V3_2") (pintype "power_in"))
      (node (ref "P1") (pin "4") (pinfunction "4_4") (pintype "passive"))
      (node (ref "R19") (pin "1") (pinfunction "1_1") (pintype "passive"))
      (node (ref "R25") (pin "1") (pinfunction "1_1") (pintype "passive"))
      (node (ref "U1") (pin "20") (pinfunction "20_20") (pintype "passive"))
      (node (ref "U6") (pin "2") (pinfunction "VOUT_2") (pintype "passive"))
      (node (ref "U6") (pin "4") (pinfunction "VOUT_4") (pintype "passive"))
    )
    (net (code "43") (name "GND") (class "Default")
      (node (ref "C1") (pin "N") (pinfunction "N_N") (pintype "passive"))
      (node (ref "C2") (pin "2") (pinfunction "2_2") (pintype "passive"))
      (node (ref "C3") (pin "1") (pinfunction "C_1") (pintype "passive"))
      (node (ref "C4") (pin "2") (pinfunction "2_2") (pintype "passive"))
      (node (ref "D2") (pin "A") (pinfunction "A_A") (pintype "passive"))
      (node (ref "D3") (pin "A") (pinfunction "A_A") (pintype "passive"))
      (node (ref "D6") (pin "A") (pinfunction "A_A") (pintype "passive"))
      (node (ref "D7") (pin "A") (pinfunction "A_A") (pintype "passive"))
      (node (ref "J2") (pin "3") (pinfunction "3_3") (pintype "passive"))
      (node (ref "J3") (pin "3") (pinfunction "3_3") (pintype "passive"))
      (node (ref "J4") (pin "2") (pinfunction "2_2") (pintype "passive"))
      (node (ref "J8") (pin "1") (pinfunction "1_1") (pintype "passive"))
      (node (ref "J9") (pin "1") (pinfunction "1_1") (pintype "passive"))
      (node (ref "MD1") (pin "1") (pinfunction "GND_1") (pintype "power_in"))
      (node (ref "MD1") (pin "15") (pinfunction "GND_15") (pintype "power_in"))
      (node (ref "MD1") (pin "38") (pinfunction "GND_38") (pintype "power_in"))
      (node (ref "MD1") (pin "39") (pinfunction "GND_39") (pintype "power_in"))
      (node (ref "P1") (pin "1") (pinfunction "1_1") (pintype "passive"))
      (node (ref "Q1") (pin "3") (pinfunction "SOURCE_3") (pintype "passive"))
      (node (ref "Q2") (pin "3") (pinfunction "SOURCE_3") (pintype "passive"))
      (node (ref "Q3") (pin "3") (pinfunction "SOURCE_3") (pintype "passive"))
      (node (ref "Q4") (pin "3") (pinfunction "SOURCE_3") (pintype "passive"))
      (node (ref "Q5") (pin "3") (pinfunction "E_3") (pintype "passive"))
      (node (ref "R13") (pin "1") (pinfunction "1_1") (pintype "passive"))
      (node (ref "R22") (pin "1") (pinfunction "1_1") (pintype "passive"))
      (node (ref "R7") (pin "1") (pinfunction "1_1") (pintype "passive"))
      (node (ref "SW12") (pin "B") (pinfunction "B_B") (pintype "passive"))
      (node (ref "SW9") (pin "B") (pinfunction "B_B") (pintype "passive"))
      (node (ref "U1") (pin "7") (pinfunction "7_7") (pintype "passive"))
      (node (ref "U2") (pin "2") (pinfunction "CATHODE_2") (pintype "passive"))
      (node (ref "U4") (pin "2") (pinfunction "CATHODE_2") (pintype "passive"))
      (node (ref "U5") (pin "2") (pinfunction "GND_2") (pintype "power_in"))
      (node (ref "U6") (pin "1") (pinfunction "Ground_1") (pintype "power_in"))
    )
    (net (code "44") (name "GND1") (class "Default")
      (node (ref "J7") (pin "4") (pinfunction "4_4") (pintype "passive"))
      (node (ref "R11") (pin "1") (pinfunction "1_1") (pintype "passive"))
      (node (ref "R12") (pin "1") (pinfunction "1_1") (pintype "passive"))
      (node (ref "R14") (pin "1") (pinfunction "1_1") (pintype "passive"))
      (node (ref "R15") (pin "1") (pinfunction "1_1") (pintype "passive"))
      (node (ref "R23") (pin "1") (pinfunction "1_1") (pintype "passive"))
      (node (ref "R24") (pin "1") (pinfunction "1_1") (pintype "passive"))
      (node (ref "R3") (pin "1") (pinfunction "1_1") (pintype "passive"))
      (node (ref "R5") (pin "1") (pinfunction "1_1") (pintype "passive"))
      (node (ref "R8") (pin "1") (pinfunction "1_1") (pintype "passive"))
      (node (ref "R9") (pin "1") (pinfunction "1_1") (pintype "passive"))
      (node (ref "U3") (pin "7") (pinfunction "7_7") (pintype "passive"))
    )
    (net (code "45") (name "Net-(D1-A)") (class "Default")
      (node (ref "D1") (pin "2") (pinfunction "A_2") (pintype "passive"))
      (node (ref "DS1") (pin "2") (pinfunction "K_2") (pintype "passive"))
      (node (ref "J1") (pin "2") (pinfunction "2_2") (pintype "passive"))
      (node (ref "Q1") (pin "2") (pinfunction "DRAIN_2") (pintype "passive"))
      (node (ref "Q2") (pin "2") (pinfunction "DRAIN_2") (pintype "passive"))
    )
    (net (code "46") (name "Net-(D4-K)") (class "Default")
      (node (ref "D4") (pin "1") (pinfunction "K_1") (pintype "passive"))
      (node (ref "R13") (pin "2") (pinfunction "2_2") (pintype "passive"))
    )
    (net (code "47") (name "Net-(D5-A)") (class "Default")
      (node (ref "D5") (pin "2") (pinfunction "A_2") (pintype "passive"))
      (node (ref "DS2") (pin "2") (pinfunction "K_2") (pintype "passive"))
      (node (ref "J5") (pin "2") (pinfunction "2_2") (pintype "passive"))
      (node (ref "Q3") (pin "2") (pinfunction "DRAIN_2") (pintype "passive"))
      (node (ref "Q4") (pin "2") (pinfunction "DRAIN_2") (pintype "passive"))
    )
    (net (code "48") (name "Net-(DS1-A)") (class "Default")
      (node (ref "DS1") (pin "1") (pinfunction "A_1") (pintype "passive"))
      (node (ref "R2") (pin "1") (pinfunction "1_1") (pintype "passive"))
    )
    (net (code "49") (name "Net-(DS2-A)") (class "Default")
      (node (ref "DS2") (pin "1") (pinfunction "A_1") (pintype "passive"))
      (node (ref "R17") (pin "1") (pinfunction "1_1") (pintype "passive"))
    )
    (net (code "50") (name "Net-(Q1-GATE)") (class "Default")
      (node (ref "D2") (pin "C") (pinfunction "C_C") (pintype "passive"))
      (node (ref "Q1") (pin "1") (pinfunction "GATE_1") (pintype "passive"))
      (node (ref "R6") (pin "2") (pinfunction "2_2") (pintype "passive"))
    )
    (net (code "51") (name "Net-(Q2-GATE)") (class "Default")
      (node (ref "D3") (pin "C") (pinfunction "C_C") (pintype "passive"))
      (node (ref "Q2") (pin "1") (pinfunction "GATE_1") (pintype "passive"))
      (node (ref "R10") (pin "2") (pinfunction "2_2") (pintype "passive"))
    )
    (net (code "52") (name "Net-(Q3-GATE)") (class "Default")
      (node (ref "D6") (pin "C") (pinfunction "C_C") (pintype "passive"))
      (node (ref "Q3") (pin "1") (pinfunction "GATE_1") (pintype "passive"))
      (node (ref "R20") (pin "2") (pinfunction "2_2") (pintype "passive"))
    )
    (net (code "53") (name "Net-(Q4-GATE)") (class "Default")
      (node (ref "D7") (pin "C") (pinfunction "C_C") (pintype "passive"))
      (node (ref "Q4") (pin "1") (pinfunction "GATE_1") (pintype "passive"))
      (node (ref "R27") (pin "2") (pinfunction "2_2") (pintype "passive"))
    )
    (net (code "54") (name "Net-(Q5-B)") (class "Default")
      (node (ref "Q5") (pin "2") (pinfunction "B_2") (pintype "passive"))
      (node (ref "R28") (pin "2") (pinfunction "2_2") (pintype "passive"))
    )
    (net (code "55") (name "Net-(Q5-C)") (class "Default")
      (node (ref "LS1") (pin "N") (pinfunction "N_N") (pintype "passive"))
      (node (ref "Q5") (pin "1") (pinfunction "C_1") (pintype "passive"))
    )
    (net (code "56") (name "Net-(R3-Pad2)") (class "Default")
      (node (ref "R3") (pin "2") (pinfunction "2_2") (pintype "passive"))
      (node (ref "SW1") (pin "A2") (pinfunction "A2_A2") (pintype "passive"))
    )
    (net (code "57") (name "Net-(R5-Pad2)") (class "Default")
      (node (ref "R5") (pin "2") (pinfunction "2_2") (pintype "passive"))
      (node (ref "SW2") (pin "A2") (pinfunction "A2_A2") (pintype "passive"))
    )
    (net (code "58") (name "Net-(R8-Pad2)") (class "Default")
      (node (ref "R8") (pin "2") (pinfunction "2_2") (pintype "passive"))
      (node (ref "SW3") (pin "A2") (pinfunction "A2_A2") (pintype "passive"))
    )
    (net (code "59") (name "Net-(R9-Pad2)") (class "Default")
      (node (ref "R9") (pin "2") (pinfunction "2_2") (pintype "passive"))
      (node (ref "SW4") (pin "A2") (pinfunction "A2_A2") (pintype "passive"))
    )
    (net (code "60") (name "Net-(R11-Pad2)") (class "Default")
      (node (ref "R11") (pin "2") (pinfunction "2_2") (pintype "passive"))
      (node (ref "SW5") (pin "A2") (pinfunction "A2_A2") (pintype "passive"))
    )
    (net (code "61") (name "Net-(R12-Pad2)") (class "Default")
      (node (ref "R12") (pin "2") (pinfunction "2_2") (pintype "passive"))
      (node (ref "SW6") (pin "A2") (pinfunction "A2_A2") (pintype "passive"))
    )
    (net (code "62") (name "Net-(R14-Pad2)") (class "Default")
      (node (ref "R14") (pin "2") (pinfunction "2_2") (pintype "passive"))
      (node (ref "SW7") (pin "A2") (pinfunction "A2_A2") (pintype "passive"))
    )
    (net (code "63") (name "Net-(R15-Pad2)") (class "Default")
      (node (ref "R15") (pin "2") (pinfunction "2_2") (pintype "passive"))
      (node (ref "SW8") (pin "A2") (pinfunction "A2_A2") (pintype "passive"))
    )
    (net (code "64") (name "Net-(R21-Pad1)") (class "Default")
      (node (ref "R21") (pin "1") (pinfunction "1_1") (pintype "passive"))
      (node (ref "SW9") (pin "A") (pinfunction "A_A") (pintype "passive"))
    )
    (net (code "65") (name "Net-(R23-Pad2)") (class "Default")
      (node (ref "R23") (pin "2") (pinfunction "2_2") (pintype "passive"))
      (node (ref "SW10") (pin "A2") (pinfunction "A2_A2") (pintype "passive"))
    )
    (net (code "66") (name "Net-(R24-Pad2)") (class "Default")
      (node (ref "R24") (pin "2") (pinfunction "2_2") (pintype "passive"))
      (node (ref "SW11") (pin "A2") (pinfunction "A2_A2") (pintype "passive"))
    )
    (net (code "67") (name "Net-(R26-Pad1)") (class "Default")
      (node (ref "R26") (pin "1") (pinfunction "1_1") (pintype "passive"))
      (node (ref "SW12") (pin "A") (pinfunction "A_A") (pintype "passive"))
    )
    (net (code "68") (name "Net-(U2-ANODE)") (class "Default")
      (node (ref "R4") (pin "2") (pinfunction "2_2") (pintype "passive"))
      (node (ref "U2") (pin "1") (pinfunction "ANODE_1") (pintype "passive"))
    )
    (net (code "69") (name "Net-(U2-COLLECTOR)") (class "Default")
      (node (ref "R1") (pin "1") (pinfunction "1_1") (pintype "passive"))
      (node (ref "U2") (pin "4") (pinfunction "COLLECTOR_4") (pintype "passive"))
    )
    (net (code "70") (name "Net-(U2-EMITTER)") (class "Default")
      (node (ref "R10") (pin "1") (pinfunction "1_1") (pintype "passive"))
      (node (ref "R6") (pin "1") (pinfunction "1_1") (pintype "passive"))
      (node (ref "R7") (pin "2") (pinfunction "2_2") (pintype "passive"))
      (node (ref "U2") (pin "3") (pinfunction "EMITTER_3") (pintype "passive"))
    )
    (net (code "71") (name "Net-(U4-ANODE)") (class "Default")
      (node (ref "R18") (pin "2") (pinfunction "2_2") (pintype "passive"))
      (node (ref "U4") (pin "1") (pinfunction "ANODE_1") (pintype "passive"))
    )
    (net (code "72") (name "Net-(U4-COLLECTOR)") (class "Default")
      (node (ref "R16") (pin "1") (pinfunction "1_1") (pintype "passive"))
      (node (ref "U4") (pin "4") (pinfunction "COLLECTOR_4") (pintype "passive"))
    )
    (net (code "73") (name "Net-(U4-EMITTER)") (class "Default")
      (node (ref "R20") (pin "1") (pinfunction "1_1") (pintype "passive"))
      (node (ref "R22") (pin "2") (pinfunction "2_2") (pintype "passive"))
      (node (ref "R27") (pin "1") (pinfunction "1_1") (pintype "passive"))
      (node (ref "U4") (pin "3") (pinfunction "EMITTER_3") (pintype "passive"))
    )
    (net (code "74") (name "VCC") (class "Default")
      (node (ref "C2") (pin "1") (pinfunction "1_1") (pintype "passive"))
      (node (ref "D1") (pin "1") (pinfunction "C_1") (pintype "passive"))
      (node (ref "D5") (pin "1") (pinfunction "C_1") (pintype "passive"))
      (node (ref "J1") (pin "1") (pinfunction "1_1") (pintype "passive"))
      (node (ref "J5") (pin "1") (pinfunction "1_1") (pintype "passive"))
      (node (ref "J8") (pin "2") (pinfunction "2_2") (pintype "passive"))
      (node (ref "L1") (pin "2") (pinfunction "2_2") (pintype "passive"))
      (node (ref "R1") (pin "2") (pinfunction "2_2") (pintype "passive"))
      (node (ref "R16") (pin "2") (pinfunction "2_2") (pintype "passive"))
      (node (ref "R17") (pin "2") (pinfunction "2_2") (pintype "passive"))
      (node (ref "R2") (pin "2") (pinfunction "2_2") (pintype "passive"))
      (node (ref "U5") (pin "1") (pinfunction "IN_1") (pintype "power_in"))
    )
    (net (code "75") (name "unconnected-(MD1-CLK-Pad20)") (class "Default")
      (node (ref "MD1") (pin "20") (pinfunction "CLK_20") (pintype "input+no_connect"))
    )
    (net (code "76") (name "unconnected-(MD1-CMD-Pad19)") (class "Default")
      (node (ref "MD1") (pin "19") (pinfunction "CMD_19") (pintype "bidirectional+no_connect"))
    )
    (net (code "77") (name "unconnected-(MD1-IO23-Pad37)") (class "Default")
      (node (ref "MD1") (pin "37") (pinfunction "IO23_37") (pintype "bidirectional+no_connect"))
    )
    (net (code "78") (name "unconnected-(MD1-NC-Pad32)") (class "Default")
      (node (ref "MD1") (pin "32") (pinfunction "NC_32") (pintype "passive+no_connect"))
    )
    (net (code "79") (name "unconnected-(MD1-SD0-Pad21)") (class "Default")
      (node (ref "MD1") (pin "21") (pinfunction "SD0_21") (pintype "bidirectional+no_connect"))
    )
    (net (code "80") (name "unconnected-(MD1-SD1-Pad22)") (class "Default")
      (node (ref "MD1") (pin "22") (pinfunction "SD1_22") (pintype "bidirectional+no_connect"))
    )
    (net (code "81") (name "unconnected-(MD1-SD2-Pad17)") (class "Default")
      (node (ref "MD1") (pin "17") (pinfunction "SD2_17") (pintype "bidirectional+no_connect"))
    )
    (net (code "82") (name "unconnected-(MD1-SD3-Pad18)") (class "Default")
      (node (ref "MD1") (pin "18") (pinfunction "SD3_18") (pintype "bidirectional+no_connect"))
    )
    (net (code "83") (name "unconnected-(SW1-PadB2)") (class "Default")
      (node (ref "SW1") (pin "B2") (pinfunction "B2_B2") (pintype "passive+no_connect"))
    )
    (net (code "84") (name "unconnected-(SW2-PadB2)") (class "Default")
      (node (ref "SW2") (pin "B2") (pinfunction "B2_B2") (pintype "passive+no_connect"))
    )
    (net (code "85") (name "unconnected-(SW3-PadB2)") (class "Default")
      (node (ref "SW3") (pin "B2") (pinfunction "B2_B2") (pintype "passive+no_connect"))
    )
    (net (code "86") (name "unconnected-(SW4-PadB2)") (class "Default")
      (node (ref "SW4") (pin "B2") (pinfunction "B2_B2") (pintype "passive+no_connect"))
    )
    (net (code "87") (name "unconnected-(SW5-PadB2)") (class "Default")
      (node (ref "SW5") (pin "B2") (pinfunction "B2_B2") (pintype "passive+no_connect"))
    )
    (net (code "88") (name "unconnected-(SW6-PadB2)") (class "Default")
      (node (ref "SW6") (pin "B2") (pinfunction "B2_B2") (pintype "passive+no_connect"))
    )
    (net (code "89") (name "unconnected-(SW7-PadB2)") (class "Default")
      (node (ref "SW7") (pin "B2") (pinfunction "B2_B2") (pintype "passive+no_connect"))
    )
    (net (code "90") (name "unconnected-(SW8-PadB2)") (class "Default")
      (node (ref "SW8") (pin "B2") (pinfunction "B2_B2") (pintype "passive+no_connect"))
    )
    (net (code "91") (name "unconnected-(SW10-PadB2)") (class "Default")
      (node (ref "SW10") (pin "B2") (pinfunction "B2_B2") (pintype "passive+no_connect"))
    )
    (net (code "92") (name "unconnected-(SW11-PadB2)") (class "Default")
      (node (ref "SW11") (pin "B2") (pinfunction "B2_B2") (pintype "passive+no_connect"))
    )
    (net (code "93") (name "unconnected-(U1-Pad9)") (class "Default")
      (node (ref "U1") (pin "9") (pinfunction "9_9") (pintype "passive+no_connect"))
    )
    (net (code "94") (name "unconnected-(U1-Pad10)") (class "Default")
      (node (ref "U1") (pin "10") (pinfunction "10_10") (pintype "passive+no_connect"))
    )
    (net (code "95") (name "unconnected-(U1-Pad11)") (class "Default")
      (node (ref "U1") (pin "11") (pinfunction "11_11") (pintype "passive+no_connect"))
    )
    (net (code "96") (name "unconnected-(U1-Pad12)") (class "Default")
      (node (ref "U1") (pin "12") (pinfunction "12_12") (pintype "passive+no_connect"))
    )
    (net (code "97") (name "unconnected-(U1-Pad13)") (class "Default")
      (node (ref "U1") (pin "13") (pinfunction "13_13") (pintype "passive+no_connect"))
    )
    (net (code "98") (name "unconnected-(U1-Pad14)") (class "Default")
      (node (ref "U1") (pin "14") (pinfunction "14_14") (pintype "passive+no_connect"))
    )
    (net (code "99") (name "unconnected-(U3-Pad9)") (class "Default")
      (node (ref "U3") (pin "9") (pinfunction "9_9") (pintype "passive+no_connect"))
    )
    (net (code "100") (name "unconnected-(U3-Pad10)") (class "Default")
      (node (ref "U3") (pin "10") (pinfunction "10_10") (pintype "passive+no_connect"))
    )
    (net (code "101") (name "unconnected-(U3-Pad11)") (class "Default")
      (node (ref "U3") (pin "11") (pinfunction "11_11") (pintype "passive+no_connect"))
    )
    (net (code "102") (name "unconnected-(U3-Pad12)") (class "Default")
      (node (ref "U3") (pin "12") (pinfunction "12_12") (pintype "passive+no_connect"))
    )
    (net (code "103") (name "unconnected-(U3-Pad13)") (class "Default")
      (node (ref "U3") (pin "13") (pinfunction "13_13") (pintype "passive+no_connect"))
    )
    (net (code "104") (name "unconnected-(U3-Pad14)") (class "Default")
      (node (ref "U3") (pin "14") (pinfunction "14_14") (pintype "passive+no_connect"))
    )
  )
)
